# CR1000X_small.net
KiCad netlist of a schematic drawn in EAGLE
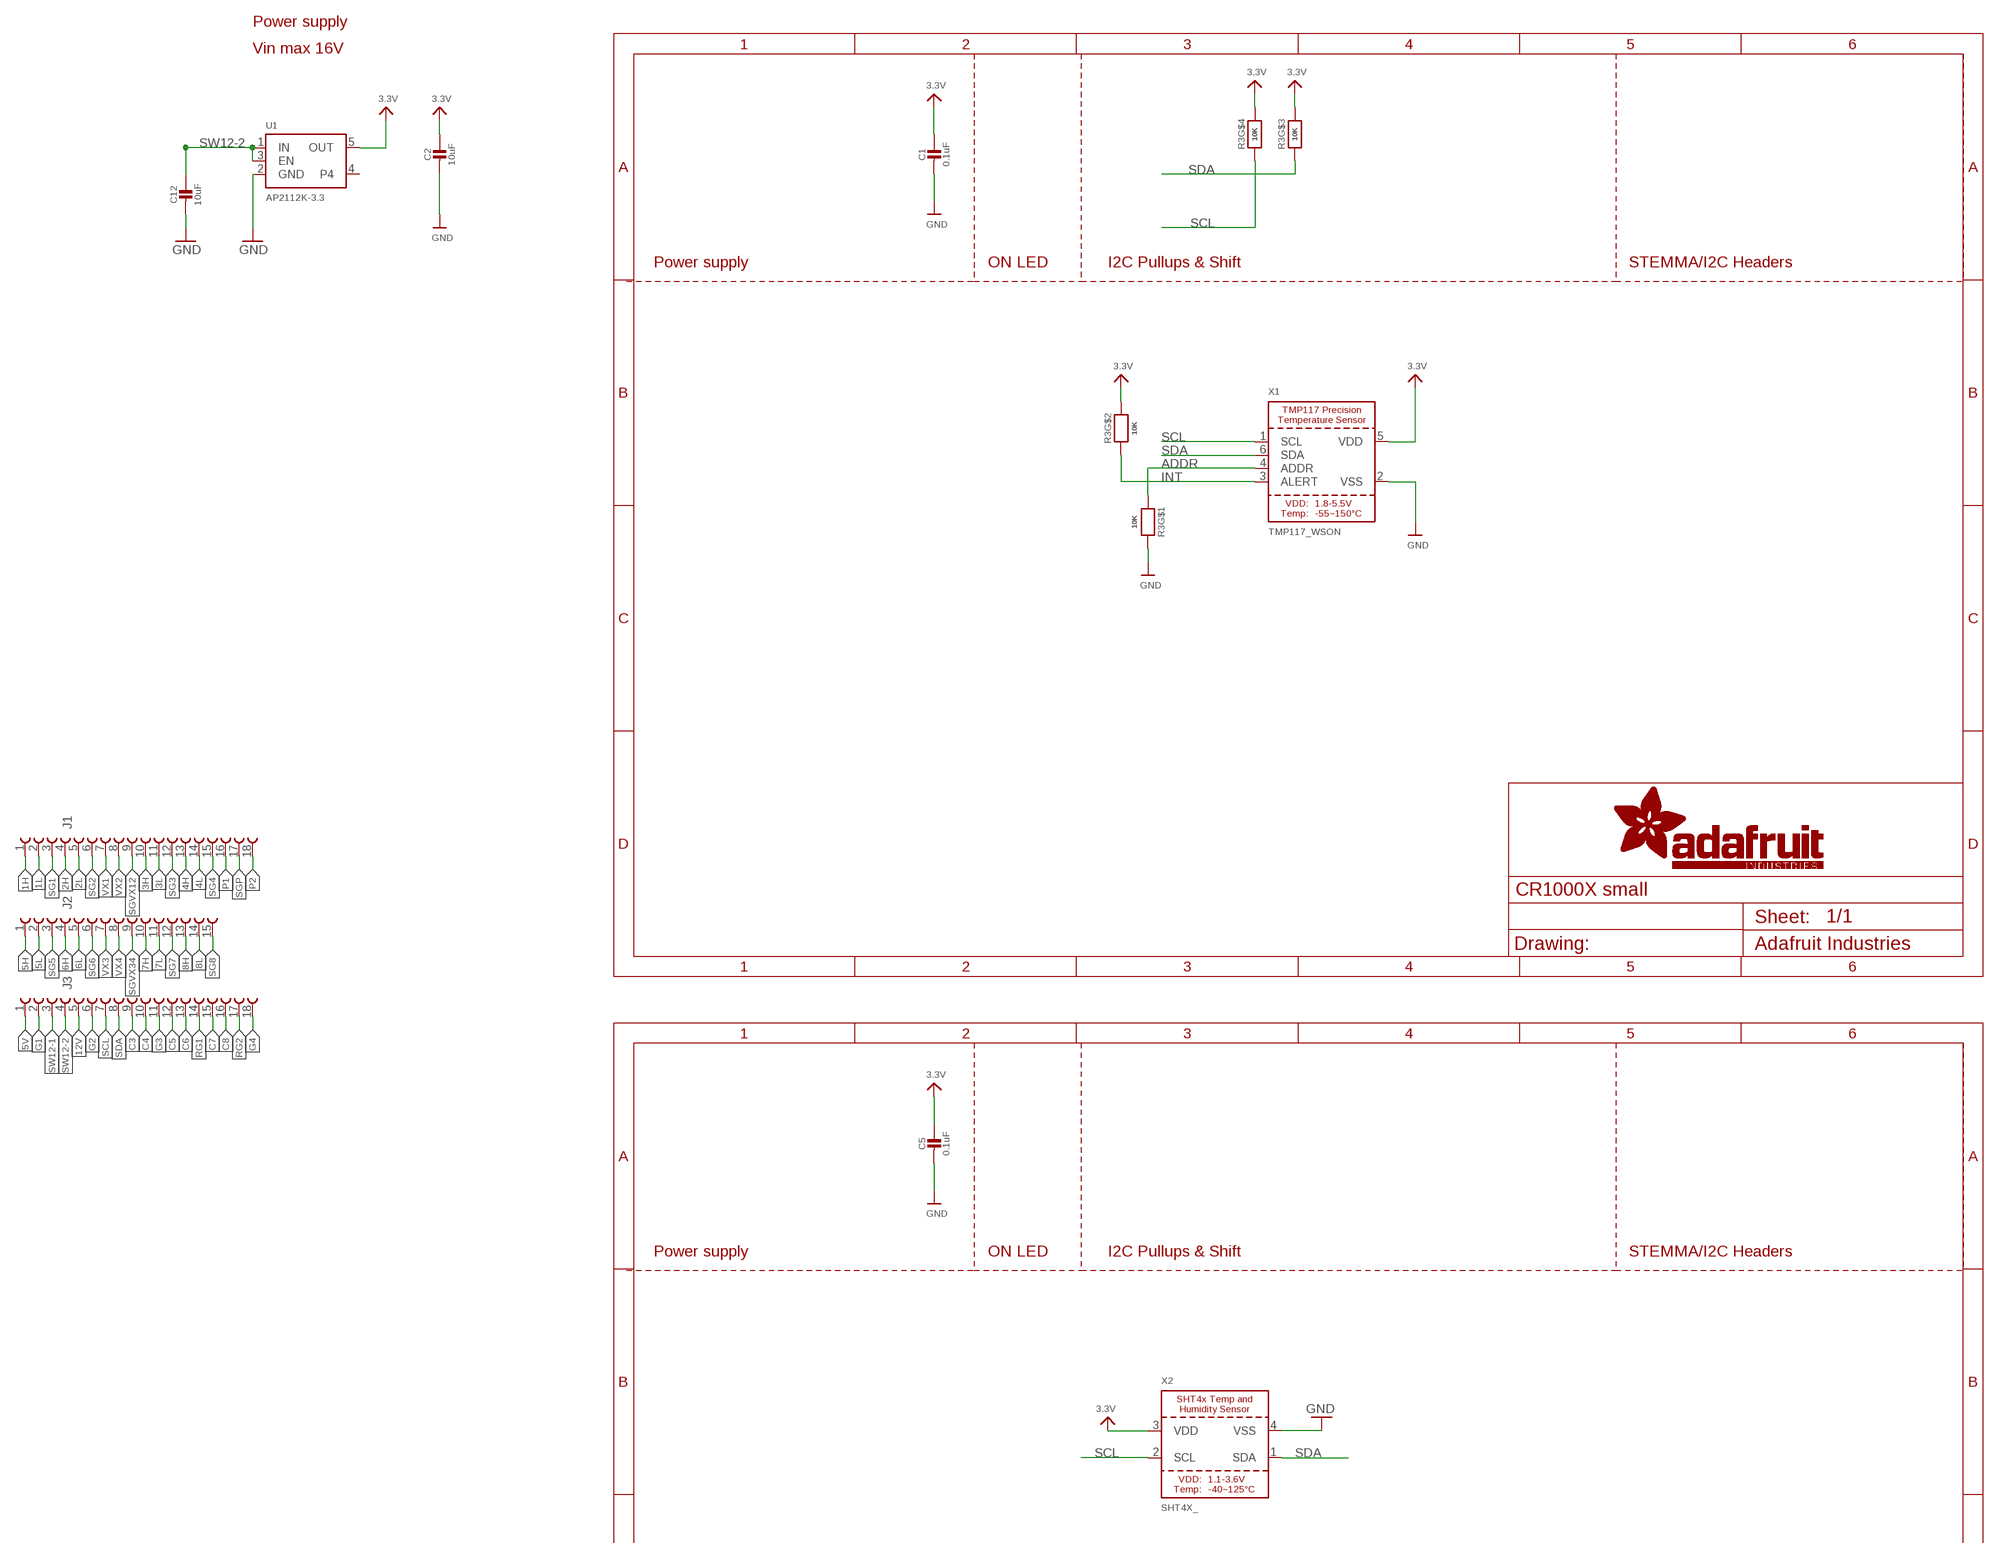
[diagram p0: schematic, sheet 1, part 1 of 2]
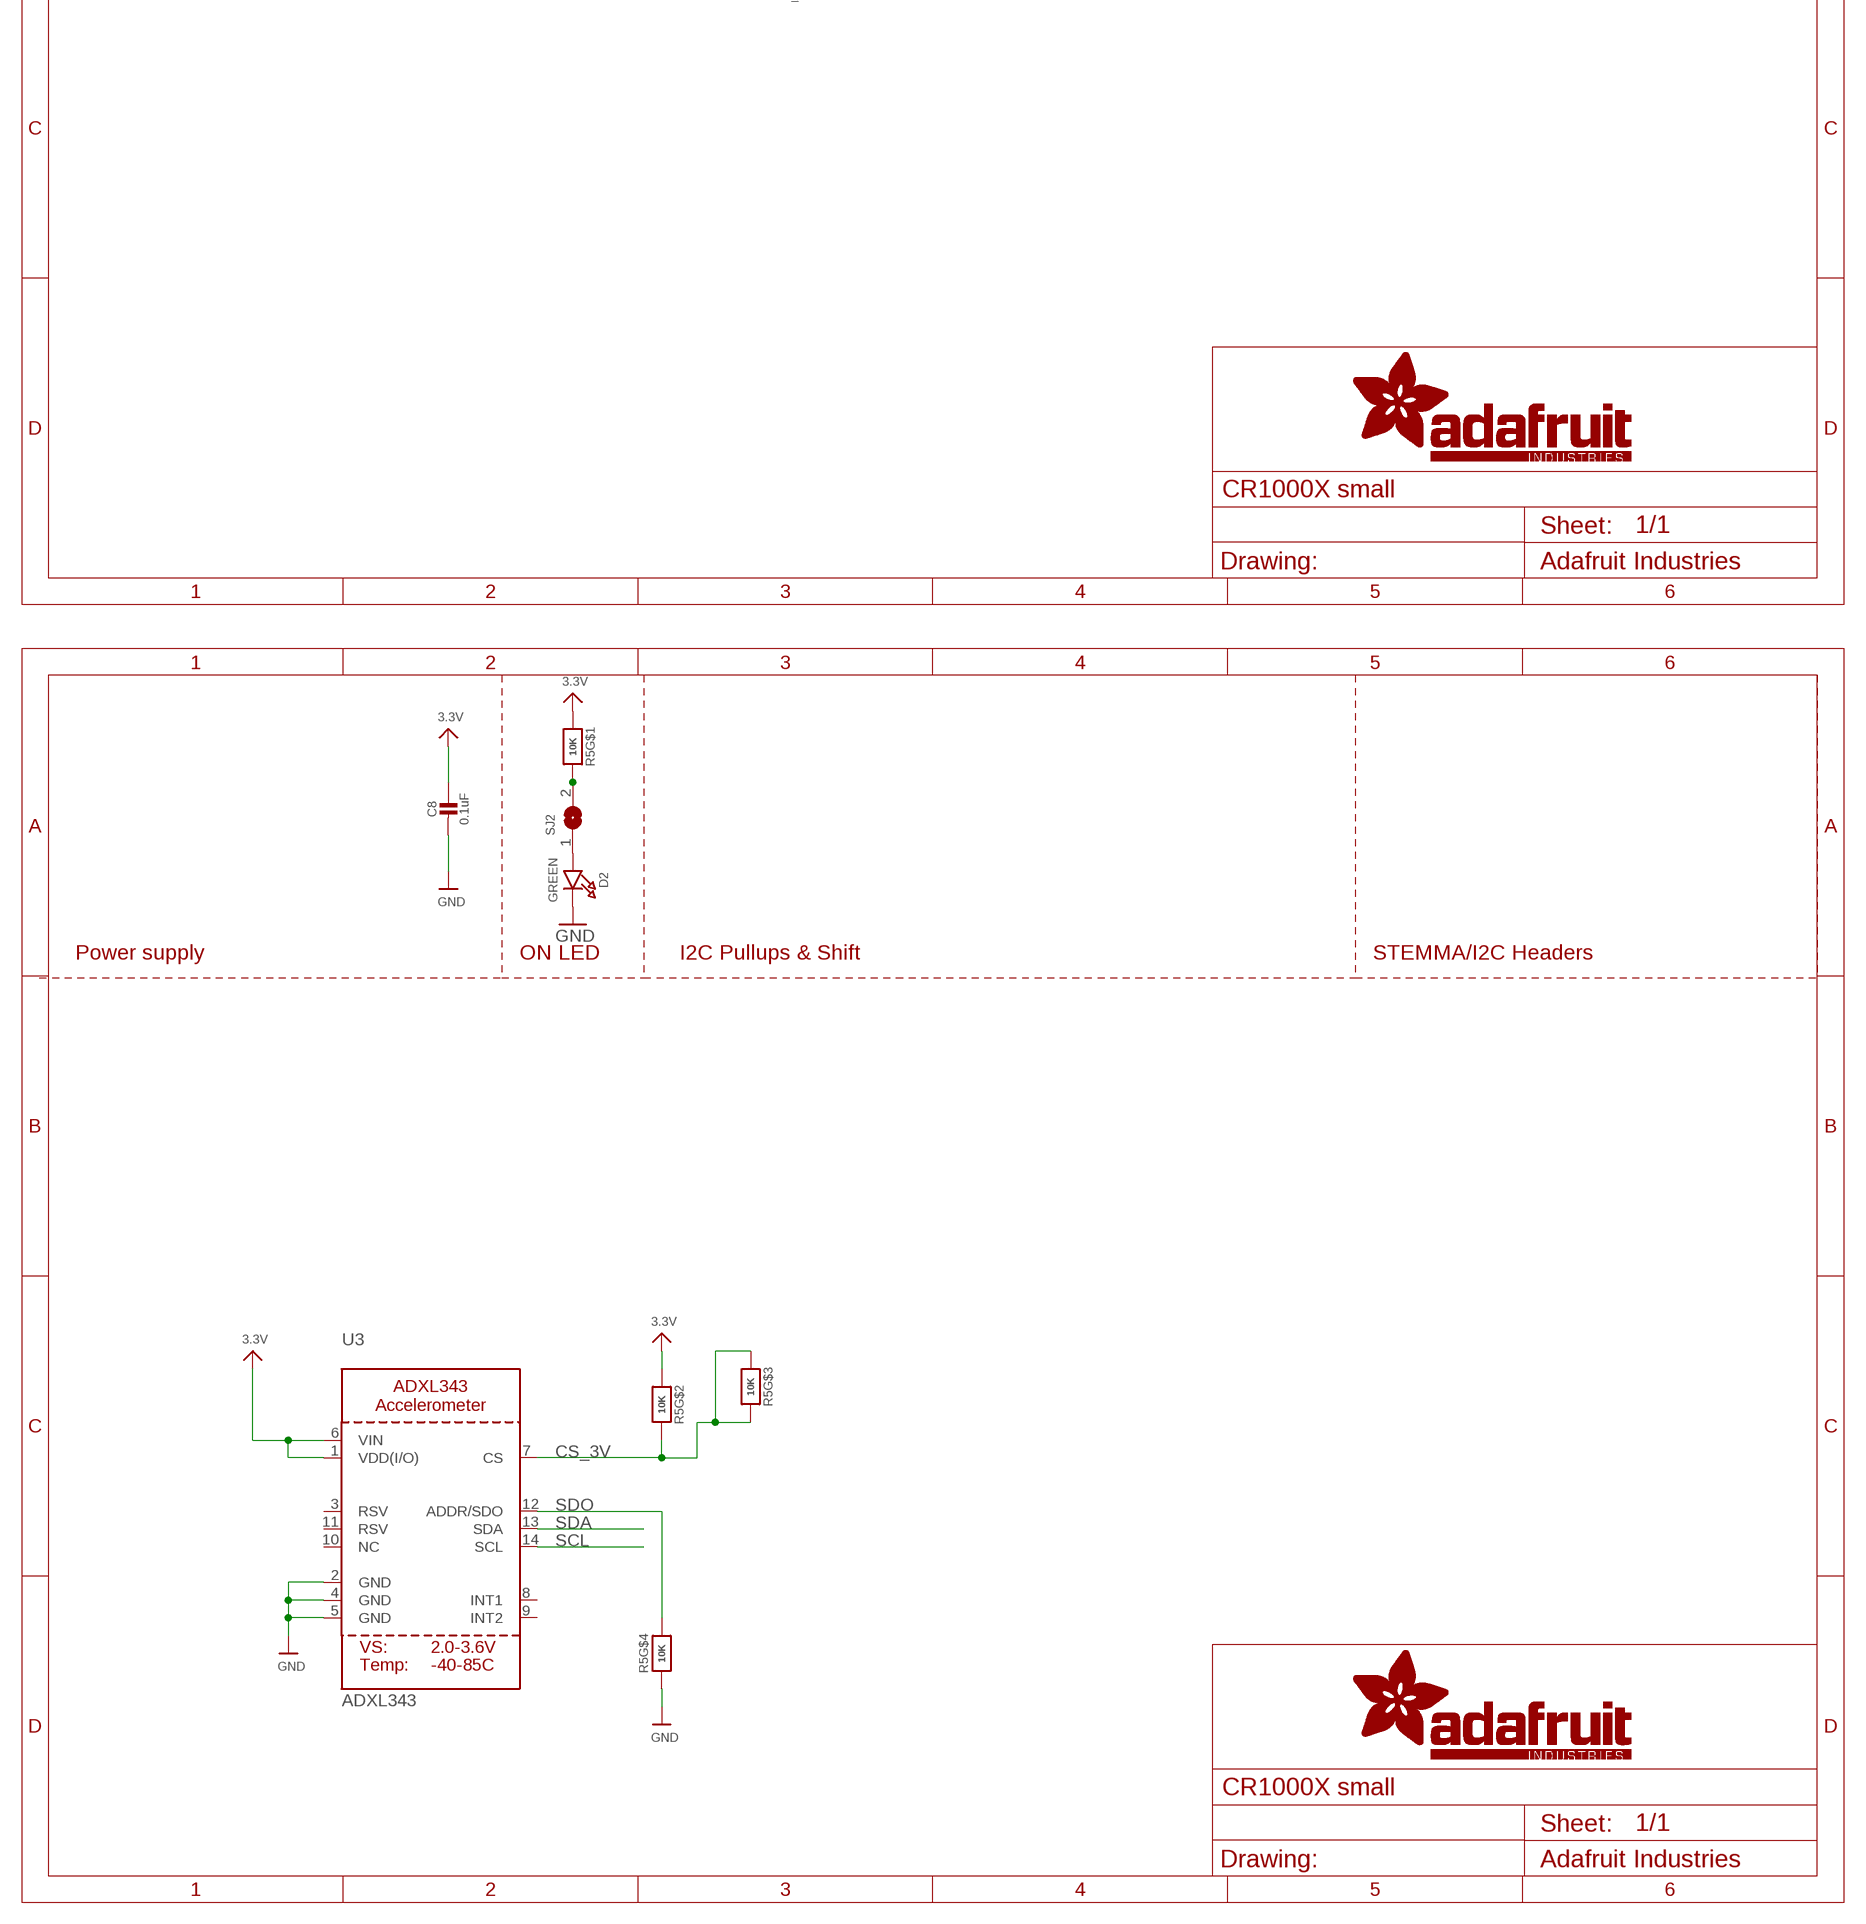
[diagram p1: schematic, sheet 1, part 2 of 2]

(export (version "E")
  (design (tool "Eeschema 10.0.6"))
  (components
    (comp (ref "C1")
      (value "0.1uF")
      (footprint "eagle-import:0603-NO")
      (libsource (lib "eagle-import") (part "CAP_CERAMIC0603_NO"))
    )
    (comp (ref "C2")
      (value "10uF")
      (footprint "eagle-import:0805-NO")
      (libsource (lib "eagle-import") (part "CAP_CERAMIC0805-NOOUTLINE"))
    )
    (comp (ref "C5")
      (value "0.1uF")
      (footprint "eagle-import:0603-NO")
      (libsource (lib "eagle-import") (part "CAP_CERAMIC0603_NO"))
    )
    (comp (ref "C8")
      (value "0.1uF")
      (footprint "eagle-import:0603-NO")
      (libsource (lib "eagle-import") (part "CAP_CERAMIC0603_NO"))
    )
    (comp (ref "C12")
      (value "10uF")
      (footprint "eagle-import:0805-NO")
      (libsource (lib "eagle-import") (part "CAP_CERAMIC0805-NOOUTLINE"))
    )
    (comp (ref "D2")
      (value "GREEN")
      (footprint "eagle-import:CHIPLED_0603_NOOUTLINE")
      (libsource (lib "eagle-import") (part "LED0603_NOOUTLINE"))
    )
    (comp (ref "J1")
      (value "691311500018")
      (footprint "eagle-import:691311500018")
      (libsource (lib "eagle-import") (part "691311500018"))
    )
    (comp (ref "J2")
      (value "691311500015")
      (footprint "eagle-import:691311500015")
      (libsource (lib "eagle-import") (part "691311500015"))
    )
    (comp (ref "J3")
      (value "691311500018")
      (footprint "eagle-import:691311500018")
      (libsource (lib "eagle-import") (part "691311500018"))
    )
    (comp (ref "R3")
      (value "10K")
      (footprint "eagle-import:RESPACK_4X0603")
      (libsource (lib "eagle-import") (part "RESISTOR_4PACK"))
    )
    (comp (ref "R5")
      (value "10K")
      (footprint "eagle-import:RESPACK_4X0603")
      (libsource (lib "eagle-import") (part "RESISTOR_4PACK"))
    )
    (comp (ref "SJ2")
      (value "SOLDERJUMPERCLOSED")
      (footprint "eagle-import:SOLDERJUMPER_CLOSEDWIRE")
      (libsource (lib "eagle-import") (part "SOLDERJUMPERCLOSED"))
    )
    (comp (ref "U1")
      (value "AP2112K-3.3")
      (footprint "eagle-import:SOT23-5")
      (libsource (lib "eagle-import") (part "VREG_SOT23-5"))
    )
    (comp (ref "U3")
      (value "ADXL343")
      (footprint "eagle-import:LGA14")
      (libsource (lib "eagle-import") (part "ACCEL_ADXL343"))
    )
    (comp (ref "X1")
      (value "TMP117_WSON")
      (footprint "eagle-import:WSON-6")
      (libsource (lib "eagle-import") (part "TMP117_WSON"))
    )
    (comp (ref "X2")
      (value "SHT4X_")
      (footprint "eagle-import:SHT4X")
      (libsource (lib "eagle-import") (part "SHT4X_"))
    )
  )
  (nets
    (net (code "1") (name "/ADDR") (class "Default")
      (node (ref "R3") (pin "1") (pinfunction "1_1") (pintype "passive"))
      (node (ref "X1") (pin "4") (pinfunction "ADDR_4") (pintype "input"))
    )
    (net (code "2") (name "/CS_3V") (class "Default")
      (node (ref "R5") (pin "3") (pinfunction "1_3") (pintype "passive"))
      (node (ref "R5") (pin "6") (pinfunction "2_6") (pintype "passive"))
      (node (ref "R5") (pin "7") (pinfunction "2_7") (pintype "passive"))
      (node (ref "U3") (pin "7") (pinfunction "CS_7") (pintype "bidirectional"))
    )
    (net (code "3") (name "/INT") (class "Default")
      (node (ref "R3") (pin "2") (pinfunction "1_2") (pintype "passive"))
      (node (ref "X1") (pin "3") (pinfunction "ALERT_3") (pintype "output"))
    )
    (net (code "4") (name "/SDO") (class "Default")
      (node (ref "R5") (pin "5") (pinfunction "2_5") (pintype "passive"))
      (node (ref "U3") (pin "12") (pinfunction "ADDR/SDO_12") (pintype "bidirectional"))
    )
    (net (code "5") (name "1H") (class "Default")
      (node (ref "J1") (pin "1") (pinfunction "1_1") (pintype "passive"))
    )
    (net (code "6") (name "1L") (class "Default")
      (node (ref "J1") (pin "2") (pinfunction "2_2") (pintype "passive"))
    )
    (net (code "7") (name "2H") (class "Default")
      (node (ref "J1") (pin "4") (pinfunction "4_4") (pintype "passive"))
    )
    (net (code "8") (name "2L") (class "Default")
      (node (ref "J1") (pin "5") (pinfunction "5_5") (pintype "passive"))
    )
    (net (code "9") (name "3.3V") (class "Default")
      (node (ref "C1") (pin "1") (pinfunction "1_1") (pintype "passive"))
      (node (ref "C2") (pin "1") (pinfunction "1_1") (pintype "passive"))
      (node (ref "C5") (pin "1") (pinfunction "1_1") (pintype "passive"))
      (node (ref "C8") (pin "1") (pinfunction "1_1") (pintype "passive"))
      (node (ref "R3") (pin "5") (pinfunction "2_5") (pintype "passive"))
      (node (ref "R3") (pin "6") (pinfunction "2_6") (pintype "passive"))
      (node (ref "R3") (pin "7") (pinfunction "2_7") (pintype "passive"))
      (node (ref "R5") (pin "1") (pinfunction "1_1") (pintype "passive"))
      (node (ref "R5") (pin "2") (pinfunction "1_2") (pintype "passive"))
      (node (ref "U1") (pin "5") (pinfunction "OUT_5") (pintype "power_in"))
      (node (ref "U3") (pin "1") (pinfunction "VDD(I/O)_1") (pintype "bidirectional"))
      (node (ref "U3") (pin "6") (pinfunction "VIN_6") (pintype "bidirectional"))
      (node (ref "X1") (pin "5") (pinfunction "VDD_5") (pintype "power_in"))
      (node (ref "X2") (pin "3") (pinfunction "VDD_3") (pintype "power_in"))
    )
    (net (code "10") (name "3H") (class "Default")
      (node (ref "J1") (pin "10") (pinfunction "10_10") (pintype "passive"))
    )
    (net (code "11") (name "3L") (class "Default")
      (node (ref "J1") (pin "11") (pinfunction "11_11") (pintype "passive"))
    )
    (net (code "12") (name "4H") (class "Default")
      (node (ref "J1") (pin "13") (pinfunction "13_13") (pintype "passive"))
    )
    (net (code "13") (name "4L") (class "Default")
      (node (ref "J1") (pin "14") (pinfunction "14_14") (pintype "passive"))
    )
    (net (code "14") (name "5H") (class "Default")
      (node (ref "J2") (pin "1") (pinfunction "1_1") (pintype "passive"))
    )
    (net (code "15") (name "5L") (class "Default")
      (node (ref "J2") (pin "2") (pinfunction "2_2") (pintype "passive"))
    )
    (net (code "16") (name "5V") (class "Default")
      (node (ref "J3") (pin "1") (pinfunction "1_1") (pintype "passive"))
    )
    (net (code "17") (name "6H") (class "Default")
      (node (ref "J2") (pin "4") (pinfunction "4_4") (pintype "passive"))
    )
    (net (code "18") (name "6L") (class "Default")
      (node (ref "J2") (pin "5") (pinfunction "5_5") (pintype "passive"))
    )
    (net (code "19") (name "7H") (class "Default")
      (node (ref "J2") (pin "10") (pinfunction "10_10") (pintype "passive"))
    )
    (net (code "20") (name "7L") (class "Default")
      (node (ref "J2") (pin "11") (pinfunction "11_11") (pintype "passive"))
    )
    (net (code "21") (name "8H") (class "Default")
      (node (ref "J2") (pin "13") (pinfunction "13_13") (pintype "passive"))
    )
    (net (code "22") (name "8L") (class "Default")
      (node (ref "J2") (pin "14") (pinfunction "14_14") (pintype "passive"))
    )
    (net (code "23") (name "12V") (class "Default")
      (node (ref "J3") (pin "5") (pinfunction "5_5") (pintype "passive"))
    )
    (net (code "24") (name "C3") (class "Default")
      (node (ref "J3") (pin "9") (pinfunction "9_9") (pintype "passive"))
    )
    (net (code "25") (name "C4") (class "Default")
      (node (ref "J3") (pin "10") (pinfunction "10_10") (pintype "passive"))
    )
    (net (code "26") (name "C5") (class "Default")
      (node (ref "J3") (pin "12") (pinfunction "12_12") (pintype "passive"))
    )
    (net (code "27") (name "C6") (class "Default")
      (node (ref "J3") (pin "13") (pinfunction "13_13") (pintype "passive"))
    )
    (net (code "28") (name "C7") (class "Default")
      (node (ref "J3") (pin "15") (pinfunction "15_15") (pintype "passive"))
    )
    (net (code "29") (name "C8") (class "Default")
      (node (ref "J3") (pin "16") (pinfunction "16_16") (pintype "passive"))
    )
    (net (code "30") (name "G1") (class "Default")
      (node (ref "J3") (pin "2") (pinfunction "2_2") (pintype "passive"))
    )
    (net (code "31") (name "G2") (class "Default")
      (node (ref "J3") (pin "6") (pinfunction "6_6") (pintype "passive"))
    )
    (net (code "32") (name "G3") (class "Default")
      (node (ref "J3") (pin "11") (pinfunction "11_11") (pintype "passive"))
    )
    (net (code "33") (name "G4") (class "Default")
      (node (ref "J3") (pin "18") (pinfunction "18_18") (pintype "passive"))
    )
    (net (code "34") (name "GND") (class "Default")
      (node (ref "C1") (pin "2") (pinfunction "2_2") (pintype "passive"))
      (node (ref "C12") (pin "2") (pinfunction "2_2") (pintype "passive"))
      (node (ref "C2") (pin "2") (pinfunction "2_2") (pintype "passive"))
      (node (ref "C5") (pin "2") (pinfunction "2_2") (pintype "passive"))
      (node (ref "C8") (pin "2") (pinfunction "2_2") (pintype "passive"))
      (node (ref "D2") (pin "C") (pinfunction "C_C") (pintype "passive"))
      (node (ref "R3") (pin "8") (pinfunction "2_8") (pintype "passive"))
      (node (ref "R5") (pin "4") (pinfunction "1_4") (pintype "passive"))
      (node (ref "U1") (pin "2") (pinfunction "GND_2") (pintype "power_in"))
      (node (ref "U3") (pin "2") (pinfunction "GND_2") (pintype "bidirectional"))
      (node (ref "U3") (pin "4") (pinfunction "GND_4") (pintype "bidirectional"))
      (node (ref "U3") (pin "5") (pinfunction "GND_5") (pintype "bidirectional"))
      (node (ref "X1") (pin "2") (pinfunction "VSS_2") (pintype "power_in"))
      (node (ref "X2") (pin "4") (pinfunction "VSS_4") (pintype "power_in"))
    )
    (net (code "35") (name "Net-(D2-PadA)") (class "Default")
      (node (ref "D2") (pin "A") (pinfunction "A_A") (pintype "passive"))
      (node (ref "SJ2") (pin "1") (pinfunction "1_1") (pintype "passive"))
    )
    (net (code "36") (name "Net-(R5A-2)") (class "Default")
      (node (ref "R5") (pin "8") (pinfunction "2_8") (pintype "passive"))
      (node (ref "SJ2") (pin "2") (pinfunction "2_2") (pintype "passive"))
    )
    (net (code "37") (name "P1") (class "Default")
      (node (ref "J1") (pin "16") (pinfunction "16_16") (pintype "passive"))
    )
    (net (code "38") (name "P2") (class "Default")
      (node (ref "J1") (pin "18") (pinfunction "18_18") (pintype "passive"))
    )
    (net (code "39") (name "RG1") (class "Default")
      (node (ref "J3") (pin "14") (pinfunction "14_14") (pintype "passive"))
    )
    (net (code "40") (name "RG2") (class "Default")
      (node (ref "J3") (pin "17") (pinfunction "17_17") (pintype "passive"))
    )
    (net (code "41") (name "SCL") (class "Default")
      (node (ref "J3") (pin "7") (pinfunction "7_7") (pintype "passive"))
      (node (ref "R3") (pin "4") (pinfunction "1_4") (pintype "passive"))
      (node (ref "U3") (pin "14") (pinfunction "SCL_14") (pintype "bidirectional"))
      (node (ref "X1") (pin "1") (pinfunction "SCL_1") (pintype "bidirectional"))
      (node (ref "X2") (pin "2") (pinfunction "SCL_2") (pintype "bidirectional"))
    )
    (net (code "42") (name "SDA") (class "Default")
      (node (ref "J3") (pin "8") (pinfunction "8_8") (pintype "passive"))
      (node (ref "R3") (pin "3") (pinfunction "1_3") (pintype "passive"))
      (node (ref "U3") (pin "13") (pinfunction "SDA_13") (pintype "bidirectional"))
      (node (ref "X1") (pin "6") (pinfunction "SDA_6") (pintype "bidirectional"))
      (node (ref "X2") (pin "1") (pinfunction "SDA_1") (pintype "bidirectional"))
    )
    (net (code "43") (name "SG1") (class "Default")
      (node (ref "J1") (pin "3") (pinfunction "3_3") (pintype "passive"))
    )
    (net (code "44") (name "SG2") (class "Default")
      (node (ref "J1") (pin "6") (pinfunction "6_6") (pintype "passive"))
    )
    (net (code "45") (name "SG3") (class "Default")
      (node (ref "J1") (pin "12") (pinfunction "12_12") (pintype "passive"))
    )
    (net (code "46") (name "SG4") (class "Default")
      (node (ref "J1") (pin "15") (pinfunction "15_15") (pintype "passive"))
    )
    (net (code "47") (name "SG5") (class "Default")
      (node (ref "J2") (pin "3") (pinfunction "3_3") (pintype "passive"))
    )
    (net (code "48") (name "SG6") (class "Default")
      (node (ref "J2") (pin "6") (pinfunction "6_6") (pintype "passive"))
    )
    (net (code "49") (name "SG7") (class "Default")
      (node (ref "J2") (pin "12") (pinfunction "12_12") (pintype "passive"))
    )
    (net (code "50") (name "SG8") (class "Default")
      (node (ref "J2") (pin "15") (pinfunction "15_15") (pintype "passive"))
    )
    (net (code "51") (name "SGP") (class "Default")
      (node (ref "J1") (pin "17") (pinfunction "17_17") (pintype "passive"))
    )
    (net (code "52") (name "SGVX12") (class "Default")
      (node (ref "J1") (pin "9") (pinfunction "9_9") (pintype "passive"))
    )
    (net (code "53") (name "SGVX34") (class "Default")
      (node (ref "J2") (pin "9") (pinfunction "9_9") (pintype "passive"))
    )
    (net (code "54") (name "SW12-1") (class "Default")
      (node (ref "J3") (pin "3") (pinfunction "3_3") (pintype "passive"))
    )
    (net (code "55") (name "SW12-2") (class "Default")
      (node (ref "C12") (pin "1") (pinfunction "1_1") (pintype "passive"))
      (node (ref "J3") (pin "4") (pinfunction "4_4") (pintype "passive"))
      (node (ref "U1") (pin "1") (pinfunction "IN_1") (pintype "power_in"))
      (node (ref "U1") (pin "3") (pinfunction "EN_3") (pintype "input"))
    )
    (net (code "56") (name "VX1") (class "Default")
      (node (ref "J1") (pin "7") (pinfunction "7_7") (pintype "passive"))
    )
    (net (code "57") (name "VX2") (class "Default")
      (node (ref "J1") (pin "8") (pinfunction "8_8") (pintype "passive"))
    )
    (net (code "58") (name "VX3") (class "Default")
      (node (ref "J2") (pin "7") (pinfunction "7_7") (pintype "passive"))
    )
    (net (code "59") (name "VX4") (class "Default")
      (node (ref "J2") (pin "8") (pinfunction "8_8") (pintype "passive"))
    )
    (net (code "60") (name "unconnected-(U1-P4-Pad4)") (class "Default")
      (node (ref "U1") (pin "4") (pinfunction "P4_4") (pintype "bidirectional"))
    )
    (net (code "61") (name "unconnected-(U3-INT1-Pad8)") (class "Default")
      (node (ref "U3") (pin "8") (pinfunction "INT1_8") (pintype "bidirectional"))
    )
    (net (code "62") (name "unconnected-(U3-INT2-Pad9)") (class "Default")
      (node (ref "U3") (pin "9") (pinfunction "INT2_9") (pintype "bidirectional"))
    )
    (net (code "63") (name "unconnected-(U3-NC-Pad10)") (class "Default")
      (node (ref "U3") (pin "10") (pinfunction "NC_10") (pintype "bidirectional"))
    )
    (net (code "64") (name "unconnected-(U3-RSV-Pad3)") (class "Default")
      (node (ref "U3") (pin "3") (pinfunction "RSV_3") (pintype "bidirectional"))
    )
    (net (code "65") (name "unconnected-(U3-RSV-Pad11)") (class "Default")
      (node (ref "U3") (pin "11") (pinfunction "RSV_11") (pintype "bidirectional"))
    )
  )
)
